# FT232.net
KiCad netlist of a schematic drawn in Altium Designer
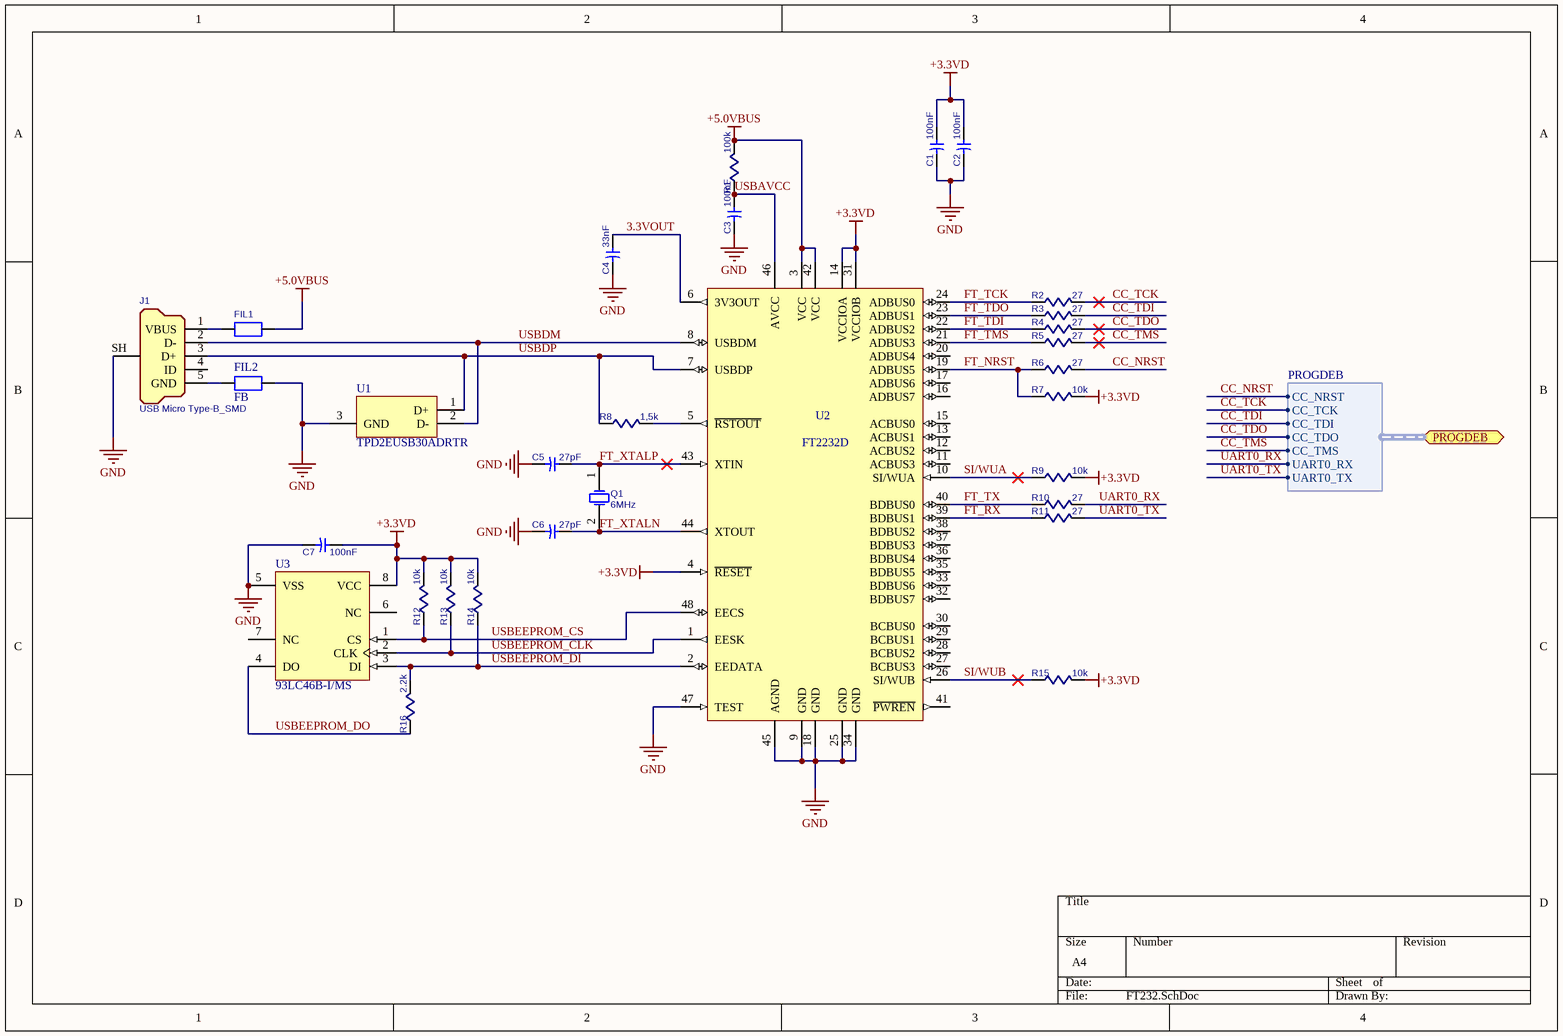
[diagram p0: FT232.SchDoc]

(export (version "E")
  (design (tool "Eeschema 10.0.6"))
  (components
    (comp (ref "C1") (value "100nF") (footprint "C_0603A") (libsource (lib "WiFi_3200") (part "C_0603")))
    (comp (ref "C2") (value "100nF") (footprint "C_0603A") (libsource (lib "WiFi_3200") (part "C_0603")))
    (comp (ref "C3") (value "100nF") (footprint "C_0603A") (libsource (lib "WiFi_3200") (part "C_0603")))
    (comp (ref "C4") (value "33nF") (footprint "C_0603A") (libsource (lib "WiFi_3200") (part "C_0603")))
    (comp (ref "C5") (value "27pF") (footprint "C_0603A") (libsource (lib "WiFi_3200") (part "C_0603")))
    (comp (ref "C6") (value "27pF") (footprint "C_0603A") (libsource (lib "WiFi_3200") (part "C_0603")))
    (comp (ref "C7") (value "100nF") (footprint "C_0603A") (libsource (lib "") (part "C_0603_1")))
    (comp (ref "FIL1")
      (value "FB")
      (footprint "FB_0603")
      (fields
        (field (name "MANUFACTURER PART NUMBER") "MPZ1608S221ATA00")
        (field (name "MANUFACTURER") "TDK Corporation")
      )
      (libsource (lib "WiFi_3200") (part "FB_0603"))
    )
    (comp (ref "FIL2")
      (value "FB")
      (footprint "FB_0603")
      (fields
        (field (name "MANUFACTURER PART NUMBER") "MPZ1608S221ATA00")
        (field (name "MANUFACTURER") "TDK Corporation")
      )
      (libsource (lib "WiFi_3200") (part "FB_0603"))
    )
    (comp (ref "J1")
      (value "USB Micro Type-B_SMD")
      (footprint "MICRO USB TYPE-B_SMD")
      (description "USB Micro Type-B")
      (fields
        (field (name "MANUFACTURER") "Amphenol FCI")
        (field (name "MANUFACTURER PART NUMBER") "10118192-0001LF")
      )
      (libsource (lib "WiFi_3200") (part "USB Micro Type-B_SMD"))
    )
    (comp (ref "Q1")
      (value "6MHz")
      (footprint "QUARTZ_10x4.5")
      (fields
        (field (name "MANUFACTURER PART NUMBER") "FQ1045A-6.000")
        (field (name "MANUFACTURER") "Fox Electronics")
      )
      (libsource (lib "WiFi_3200") (part "QUARTZ_10x4.5mm"))
    )
    (comp (ref "R1") (value "100k") (footprint "R_0603") (libsource (lib "WiFi_3200") (part "R_0603")))
    (comp (ref "R2") (value "27") (footprint "R_0603") (libsource (lib "WiFi_3200") (part "R_0603")))
    (comp (ref "R3") (value "27") (footprint "R_0603") (libsource (lib "WiFi_3200") (part "R_0603")))
    (comp (ref "R4") (value "27") (footprint "R_0603") (libsource (lib "WiFi_3200") (part "R_0603")))
    (comp (ref "R5") (value "27") (footprint "R_0603") (libsource (lib "WiFi_3200") (part "R_0603")))
    (comp (ref "R6") (value "27") (footprint "R_0603") (libsource (lib "WiFi_3200") (part "R_0603")))
    (comp (ref "R7") (value "10k") (footprint "R_0603") (libsource (lib "WiFi_3200") (part "R_0603")))
    (comp (ref "R8") (value "1,5k") (footprint "R_0603") (libsource (lib "WiFi_3200") (part "R_0603")))
    (comp (ref "R9") (value "10k") (footprint "R_0603") (libsource (lib "WiFi_3200") (part "R_0603")))
    (comp (ref "R10") (value "27") (footprint "R_0603") (libsource (lib "WiFi_3200") (part "R_0603")))
    (comp (ref "R11") (value "27") (footprint "R_0603") (libsource (lib "WiFi_3200") (part "R_0603")))
    (comp (ref "R12") (value "10k") (footprint "R_0603") (libsource (lib "WiFi_3200") (part "R_0603")))
    (comp (ref "R13") (value "10k") (footprint "R_0603") (libsource (lib "WiFi_3200") (part "R_0603")))
    (comp (ref "R14") (value "10k") (footprint "R_0603") (libsource (lib "WiFi_3200") (part "R_0603")))
    (comp (ref "R15") (value "10k") (footprint "R_0603") (libsource (lib "WiFi_3200") (part "R_0603")))
    (comp (ref "R16") (value "2.2k") (footprint "R_0603") (libsource (lib "WiFi_3200") (part "R_0603")))
    (comp (ref "U1")
      (value "TPD2EUSB30ADRTR")
      (footprint "DRT0003A")
      (fields (field (name "MANUFACTURER") "Texas Instruments"))
      (libsource (lib "Altium Content Vault") (part "TI-TPD2EUSB30A-SOT_DRT-3"))
    )
    (comp (ref "U2")
      (value "FT2232D")
      (footprint "LQFP-48_N")
      (description "FT2232D Dual USB to Serial UART/FIFO IC, -40 to +85 degC, 48-pin LQFP")
      (fields (field (name "MANUFACTURER") "FTDI"))
      (libsource (lib "Altium Content Vault") (part "COM-UART-FT2232D-SQ48"))
    )
    (comp (ref "U3")
      (value "93LC46B-I/MS")
      (footprint "MSOP-MS8_N")
      (description "1K, 64x16-bit, 2.5V Microwire Serial EEPROM, 8-Pin MSOP, Industrial Temperature")
      (libsource (lib "Altium Content Vault") (part "MEM-SEEPROM-93AA46B-P-8"))
    )
  )
  (nets
    (net (code "2") (name "+3.3VD") (class "Default")
      (node (ref "C1") (pin "1") (pinfunction "1_1") (pintype "passive"))
      (node (ref "C2") (pin "1") (pinfunction "1_1") (pintype "passive"))
      (node (ref "C7") (pin "1") (pinfunction "1_1") (pintype "passive"))
      (node (ref "R12") (pin "1") (pinfunction "1_1") (pintype "passive"))
      (node (ref "R13") (pin "1") (pinfunction "1_1") (pintype "passive"))
      (node (ref "R14") (pin "1") (pinfunction "1_1") (pintype "passive"))
      (node (ref "R15") (pin "1") (pinfunction "1_1") (pintype "passive"))
      (node (ref "R7") (pin "1") (pinfunction "1_1") (pintype "passive"))
      (node (ref "R9") (pin "1") (pinfunction "1_1") (pintype "passive"))
      (node (ref "U2") (pin "14") (pinfunction "VCCIOA_14") (pintype "power_in"))
      (node (ref "U2") (pin "31") (pinfunction "VCCIOB_31") (pintype "power_in"))
      (node (ref "U2") (pin "4") (pinfunction "~{RESET}_4") (pintype "input"))
      (node (ref "U3") (pin "8") (pinfunction "VCC_8") (pintype "power_in"))
    )
    (net (code "3") (name "+5.0VBUS") (class "Default")
      (node (ref "FIL1") (pin "1") (pinfunction "1_1") (pintype "passive"))
      (node (ref "R1") (pin "1") (pinfunction "1_1") (pintype "passive"))
      (node (ref "U2") (pin "3") (pinfunction "VCC_3") (pintype "power_in"))
      (node (ref "U2") (pin "42") (pinfunction "VCC_42") (pintype "power_in"))
    )
    (net (code "4") (name "/3.3VOUT") (class "Default")
      (node (ref "C4") (pin "1") (pinfunction "1_1") (pintype "passive"))
      (node (ref "U2") (pin "6") (pinfunction "3V3OUT_6") (pintype "output"))
    )
    (net (code "5") (name "/CC_NRST") (class "Default")
      (node (ref "R6") (pin "1") (pinfunction "1_1") (pintype "passive"))
    )
    (net (code "6") (name "/CC_TCK") (class "Default")
      (node (ref "R2") (pin "1") (pinfunction "1_1") (pintype "passive"))
    )
    (net (code "7") (name "/CC_TDI") (class "Default")
      (node (ref "R3") (pin "1") (pinfunction "1_1") (pintype "passive"))
    )
    (net (code "8") (name "/CC_TDO") (class "Default")
      (node (ref "R4") (pin "1") (pinfunction "1_1") (pintype "passive"))
    )
    (net (code "9") (name "/CC_TMS") (class "Default")
      (node (ref "R5") (pin "1") (pinfunction "1_1") (pintype "passive"))
    )
    (net (code "10") (name "/FT_NRST") (class "Default")
      (node (ref "R6") (pin "2") (pinfunction "2_2") (pintype "passive"))
      (node (ref "R7") (pin "2") (pinfunction "2_2") (pintype "passive"))
      (node (ref "U2") (pin "19") (pinfunction "ADBUS5_19") (pintype "bidirectional"))
    )
    (net (code "11") (name "/FT_RX") (class "Default")
      (node (ref "R11") (pin "2") (pinfunction "2_2") (pintype "passive"))
      (node (ref "U2") (pin "39") (pinfunction "BDBUS1_39") (pintype "bidirectional"))
    )
    (net (code "12") (name "/FT_TCK") (class "Default")
      (node (ref "R2") (pin "2") (pinfunction "2_2") (pintype "passive"))
      (node (ref "U2") (pin "24") (pinfunction "ADBUS0_24") (pintype "bidirectional"))
    )
    (net (code "13") (name "/FT_TDI") (class "Default")
      (node (ref "R4") (pin "2") (pinfunction "2_2") (pintype "passive"))
      (node (ref "U2") (pin "22") (pinfunction "ADBUS2_22") (pintype "bidirectional"))
    )
    (net (code "14") (name "/FT_TDO") (class "Default")
      (node (ref "R3") (pin "2") (pinfunction "2_2") (pintype "passive"))
      (node (ref "U2") (pin "23") (pinfunction "ADBUS1_23") (pintype "bidirectional"))
    )
    (net (code "15") (name "/FT_TMS") (class "Default")
      (node (ref "R5") (pin "2") (pinfunction "2_2") (pintype "passive"))
      (node (ref "U2") (pin "21") (pinfunction "ADBUS3_21") (pintype "bidirectional"))
    )
    (net (code "16") (name "/FT_TX") (class "Default")
      (node (ref "R10") (pin "2") (pinfunction "2_2") (pintype "passive"))
      (node (ref "U2") (pin "40") (pinfunction "BDBUS0_40") (pintype "bidirectional"))
    )
    (net (code "17") (name "/FT_XTALN") (class "Default")
      (node (ref "C6") (pin "1") (pinfunction "1_1") (pintype "passive"))
      (node (ref "Q1") (pin "2") (pinfunction "X2_2") (pintype "passive"))
      (node (ref "U2") (pin "44") (pinfunction "XTOUT_44") (pintype "output"))
    )
    (net (code "18") (name "/FT_XTALP") (class "Default")
      (node (ref "C5") (pin "1") (pinfunction "1_1") (pintype "passive"))
      (node (ref "Q1") (pin "1") (pinfunction "X1_1") (pintype "passive"))
      (node (ref "U2") (pin "43") (pinfunction "XTIN_43") (pintype "input"))
    )
    (net (code "19") (name "/SI{slash}WUA") (class "Default")
      (node (ref "R9") (pin "2") (pinfunction "2_2") (pintype "passive"))
      (node (ref "U2") (pin "10") (pinfunction "SI/WUA_10") (pintype "input"))
    )
    (net (code "20") (name "/SI{slash}WUB") (class "Default")
      (node (ref "R15") (pin "2") (pinfunction "2_2") (pintype "passive"))
      (node (ref "U2") (pin "26") (pinfunction "SI/WUB_26") (pintype "input"))
    )
    (net (code "21") (name "/UART0_RX") (class "Default")
      (node (ref "R10") (pin "1") (pinfunction "1_1") (pintype "passive"))
    )
    (net (code "22") (name "/UART0_TX") (class "Default")
      (node (ref "R11") (pin "1") (pinfunction "1_1") (pintype "passive"))
    )
    (net (code "23") (name "/USBAVCC") (class "Default")
      (node (ref "C3") (pin "1") (pinfunction "1_1") (pintype "passive"))
      (node (ref "R1") (pin "2") (pinfunction "2_2") (pintype "passive"))
      (node (ref "U2") (pin "46") (pinfunction "AVCC_46") (pintype "power_in"))
    )
    (net (code "24") (name "/USBDM") (class "Default")
      (node (ref "J1") (pin "2") (pinfunction "D-_2") (pintype "passive"))
      (node (ref "U1") (pin "2") (pinfunction "D-_2") (pintype "passive"))
      (node (ref "U2") (pin "8") (pinfunction "USBDM_8") (pintype "bidirectional"))
    )
    (net (code "25") (name "/USBDP") (class "Default")
      (node (ref "J1") (pin "3") (pinfunction "D+_3") (pintype "passive"))
      (node (ref "R8") (pin "2") (pinfunction "2_2") (pintype "passive"))
      (node (ref "U1") (pin "1") (pinfunction "D+_1") (pintype "passive"))
      (node (ref "U2") (pin "7") (pinfunction "USBDP_7") (pintype "bidirectional"))
    )
    (net (code "26") (name "/USBEEPROM_CLK") (class "Default")
      (node (ref "R13") (pin "2") (pinfunction "2_2") (pintype "passive"))
      (node (ref "U2") (pin "1") (pinfunction "EESK_1") (pintype "output"))
      (node (ref "U3") (pin "2") (pinfunction "CLK_2") (pintype "input"))
    )
    (net (code "27") (name "/USBEEPROM_CS") (class "Default")
      (node (ref "R12") (pin "2") (pinfunction "2_2") (pintype "passive"))
      (node (ref "U2") (pin "48") (pinfunction "EECS_48") (pintype "bidirectional"))
      (node (ref "U3") (pin "1") (pinfunction "CS_1") (pintype "input"))
    )
    (net (code "28") (name "/USBEEPROM_DI") (class "Default")
      (node (ref "R14") (pin "2") (pinfunction "2_2") (pintype "passive"))
      (node (ref "R16") (pin "1") (pinfunction "1_1") (pintype "passive"))
      (node (ref "U2") (pin "2") (pinfunction "EEDATA_2") (pintype "bidirectional"))
      (node (ref "U3") (pin "3") (pinfunction "DI_3") (pintype "input"))
    )
    (net (code "29") (name "/USBEEPROM_DO") (class "Default")
      (node (ref "R16") (pin "2") (pinfunction "2_2") (pintype "passive"))
      (node (ref "U3") (pin "4") (pinfunction "DO_4") (pintype "tri_state"))
    )
    (net (code "31") (name "GND") (class "Default")
      (node (ref "C1") (pin "2") (pinfunction "2_2") (pintype "passive"))
      (node (ref "C2") (pin "2") (pinfunction "2_2") (pintype "passive"))
      (node (ref "C3") (pin "2") (pinfunction "2_2") (pintype "passive"))
      (node (ref "C4") (pin "2") (pinfunction "2_2") (pintype "passive"))
      (node (ref "C5") (pin "2") (pinfunction "2_2") (pintype "passive"))
      (node (ref "C6") (pin "2") (pinfunction "2_2") (pintype "passive"))
      (node (ref "C7") (pin "2") (pinfunction "2_2") (pintype "passive"))
      (node (ref "FIL2") (pin "1") (pinfunction "1_1") (pintype "passive"))
      (node (ref "J1") (pin "SH") (pinfunction "Shell_SH") (pintype "passive"))
      (node (ref "U1") (pin "3") (pinfunction "GND_3") (pintype "power_in"))
      (node (ref "U2") (pin "18") (pinfunction "GND_18") (pintype "power_in"))
      (node (ref "U2") (pin "25") (pinfunction "GND_25") (pintype "power_in"))
      (node (ref "U2") (pin "34") (pinfunction "GND_34") (pintype "power_in"))
      (node (ref "U2") (pin "45") (pinfunction "AGND_45") (pintype "power_in"))
      (node (ref "U2") (pin "47") (pinfunction "TEST_47") (pintype "input"))
      (node (ref "U2") (pin "9") (pinfunction "GND_9") (pintype "power_in"))
      (node (ref "U3") (pin "5") (pinfunction "VSS_5") (pintype "power_in"))
    )
    (net (code "32") (name "Net-(J1-GND)") (class "Default")
      (node (ref "FIL2") (pin "2") (pinfunction "2_2") (pintype "passive"))
      (node (ref "J1") (pin "5") (pinfunction "GND_5") (pintype "passive"))
    )
    (net (code "33") (name "Net-(J1-VBUS)") (class "Default")
      (node (ref "FIL1") (pin "2") (pinfunction "2_2") (pintype "passive"))
      (node (ref "J1") (pin "1") (pinfunction "VBUS_1") (pintype "passive"))
    )
    (net (code "34") (name "Net-(U2-~{RSTOUT})") (class "Default")
      (node (ref "R8") (pin "1") (pinfunction "1_1") (pintype "passive"))
      (node (ref "U2") (pin "5") (pinfunction "~{RSTOUT}_5") (pintype "output"))
    )
    (net (code "35") (name "unconnected-(J1-ID-Pad4)") (class "Default")
      (node (ref "J1") (pin "4") (pinfunction "ID_4") (pintype "passive"))
    )
    (net (code "36") (name "unconnected-(U2-ACBUS0-Pad15)") (class "Default")
      (node (ref "U2") (pin "15") (pinfunction "ACBUS0_15") (pintype "bidirectional"))
    )
    (net (code "37") (name "unconnected-(U2-ACBUS1-Pad13)") (class "Default")
      (node (ref "U2") (pin "13") (pinfunction "ACBUS1_13") (pintype "bidirectional"))
    )
    (net (code "38") (name "unconnected-(U2-ACBUS2-Pad12)") (class "Default")
      (node (ref "U2") (pin "12") (pinfunction "ACBUS2_12") (pintype "bidirectional"))
    )
    (net (code "39") (name "unconnected-(U2-ACBUS3-Pad11)") (class "Default")
      (node (ref "U2") (pin "11") (pinfunction "ACBUS3_11") (pintype "bidirectional"))
    )
    (net (code "40") (name "unconnected-(U2-ADBUS4-Pad20)") (class "Default")
      (node (ref "U2") (pin "20") (pinfunction "ADBUS4_20") (pintype "bidirectional"))
    )
    (net (code "41") (name "unconnected-(U2-ADBUS6-Pad17)") (class "Default")
      (node (ref "U2") (pin "17") (pinfunction "ADBUS6_17") (pintype "bidirectional"))
    )
    (net (code "42") (name "unconnected-(U2-ADBUS7-Pad16)") (class "Default")
      (node (ref "U2") (pin "16") (pinfunction "ADBUS7_16") (pintype "bidirectional"))
    )
    (net (code "43") (name "unconnected-(U2-BCBUS0-Pad30)") (class "Default")
      (node (ref "U2") (pin "30") (pinfunction "BCBUS0_30") (pintype "bidirectional"))
    )
    (net (code "44") (name "unconnected-(U2-BCBUS1-Pad29)") (class "Default")
      (node (ref "U2") (pin "29") (pinfunction "BCBUS1_29") (pintype "bidirectional"))
    )
    (net (code "45") (name "unconnected-(U2-BCBUS2-Pad28)") (class "Default")
      (node (ref "U2") (pin "28") (pinfunction "BCBUS2_28") (pintype "bidirectional"))
    )
    (net (code "46") (name "unconnected-(U2-BCBUS3-Pad27)") (class "Default")
      (node (ref "U2") (pin "27") (pinfunction "BCBUS3_27") (pintype "bidirectional"))
    )
    (net (code "47") (name "unconnected-(U2-BDBUS2-Pad38)") (class "Default")
      (node (ref "U2") (pin "38") (pinfunction "BDBUS2_38") (pintype "bidirectional"))
    )
    (net (code "48") (name "unconnected-(U2-BDBUS3-Pad37)") (class "Default")
      (node (ref "U2") (pin "37") (pinfunction "BDBUS3_37") (pintype "bidirectional"))
    )
    (net (code "49") (name "unconnected-(U2-BDBUS4-Pad36)") (class "Default")
      (node (ref "U2") (pin "36") (pinfunction "BDBUS4_36") (pintype "bidirectional"))
    )
    (net (code "50") (name "unconnected-(U2-BDBUS5-Pad35)") (class "Default")
      (node (ref "U2") (pin "35") (pinfunction "BDBUS5_35") (pintype "bidirectional"))
    )
    (net (code "51") (name "unconnected-(U2-BDBUS6-Pad33)") (class "Default")
      (node (ref "U2") (pin "33") (pinfunction "BDBUS6_33") (pintype "bidirectional"))
    )
    (net (code "52") (name "unconnected-(U2-BDBUS7-Pad32)") (class "Default")
      (node (ref "U2") (pin "32") (pinfunction "BDBUS7_32") (pintype "bidirectional"))
    )
    (net (code "53") (name "unconnected-(U2-~{PWREN}-Pad41)") (class "Default")
      (node (ref "U2") (pin "41") (pinfunction "~{PWREN}_41") (pintype "output"))
    )
    (net (code "54") (name "unconnected-(U3-NC-Pad6)") (class "Default")
      (node (ref "U3") (pin "6") (pinfunction "NC_6") (pintype "passive"))
    )
    (net (code "55") (name "unconnected-(U3-NC-Pad7)") (class "Default")
      (node (ref "U3") (pin "7") (pinfunction "NC_7") (pintype "passive"))
    )
  )
)
